# input2.net
KiCad netlist of a schematic drawn in Altium Designer
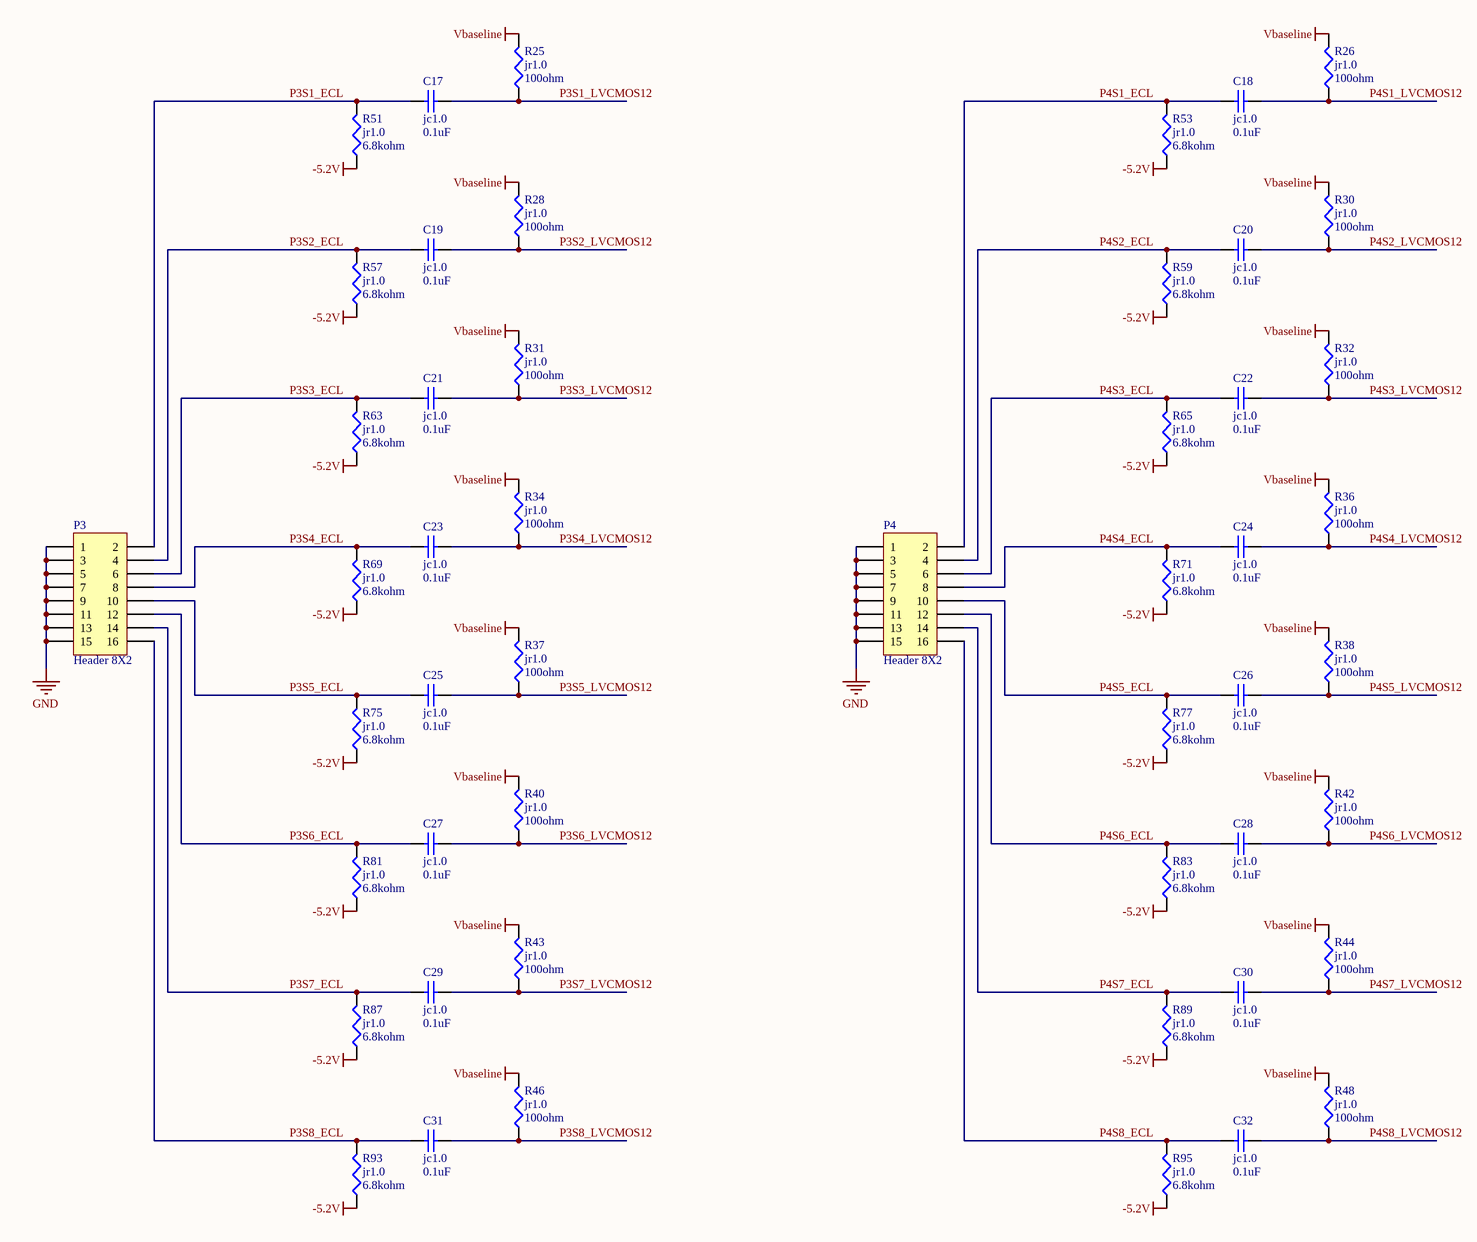
[diagram p0: input2.SchDoc]

(export (version "E")
  (design (tool "Eeschema 10.0.6"))
  (components
    (comp (ref "C17")
      (value "jc1.0")
      (footprint "0402")
      (description "Capacitor")
      (fields (field (name "ALTIUM_VALUE") "0.1uF") (field (name "PUBLISHER") "Altium Limited"))
      (libsource (lib "LIB01DXP2006SchLib") (part "Cap"))
    )
    (comp (ref "C18")
      (value "jc1.0")
      (footprint "0402")
      (description "Capacitor")
      (fields (field (name "ALTIUM_VALUE") "0.1uF") (field (name "PUBLISHER") "Altium Limited"))
      (libsource (lib "LIB01DXP2006SchLib") (part "Cap"))
    )
    (comp (ref "C19")
      (value "jc1.0")
      (footprint "0402")
      (description "Capacitor")
      (fields (field (name "ALTIUM_VALUE") "0.1uF") (field (name "PUBLISHER") "Altium Limited"))
      (libsource (lib "LIB01DXP2006SchLib") (part "Cap"))
    )
    (comp (ref "C20")
      (value "jc1.0")
      (footprint "0402")
      (description "Capacitor")
      (fields (field (name "ALTIUM_VALUE") "0.1uF") (field (name "PUBLISHER") "Altium Limited"))
      (libsource (lib "LIB01DXP2006SchLib") (part "Cap"))
    )
    (comp (ref "C21")
      (value "jc1.0")
      (footprint "0402")
      (description "Capacitor")
      (fields (field (name "ALTIUM_VALUE") "0.1uF") (field (name "PUBLISHER") "Altium Limited"))
      (libsource (lib "LIB01DXP2006SchLib") (part "Cap"))
    )
    (comp (ref "C22")
      (value "jc1.0")
      (footprint "0402")
      (description "Capacitor")
      (fields (field (name "ALTIUM_VALUE") "0.1uF") (field (name "PUBLISHER") "Altium Limited"))
      (libsource (lib "LIB01DXP2006SchLib") (part "Cap"))
    )
    (comp (ref "C23")
      (value "jc1.0")
      (footprint "0402")
      (description "Capacitor")
      (fields (field (name "ALTIUM_VALUE") "0.1uF") (field (name "PUBLISHER") "Altium Limited"))
      (libsource (lib "LIB01DXP2006SchLib") (part "Cap"))
    )
    (comp (ref "C24")
      (value "jc1.0")
      (footprint "0402")
      (description "Capacitor")
      (fields (field (name "ALTIUM_VALUE") "0.1uF") (field (name "PUBLISHER") "Altium Limited"))
      (libsource (lib "LIB01DXP2006SchLib") (part "Cap"))
    )
    (comp (ref "C25")
      (value "jc1.0")
      (footprint "0402")
      (description "Capacitor")
      (fields (field (name "ALTIUM_VALUE") "0.1uF") (field (name "PUBLISHER") "Altium Limited"))
      (libsource (lib "LIB01DXP2006SchLib") (part "Cap"))
    )
    (comp (ref "C26")
      (value "jc1.0")
      (footprint "0402")
      (description "Capacitor")
      (fields (field (name "ALTIUM_VALUE") "0.1uF") (field (name "PUBLISHER") "Altium Limited"))
      (libsource (lib "LIB01DXP2006SchLib") (part "Cap"))
    )
    (comp (ref "C27")
      (value "jc1.0")
      (footprint "0402")
      (description "Capacitor")
      (fields (field (name "ALTIUM_VALUE") "0.1uF") (field (name "PUBLISHER") "Altium Limited"))
      (libsource (lib "LIB01DXP2006SchLib") (part "Cap"))
    )
    (comp (ref "C28")
      (value "jc1.0")
      (footprint "0402")
      (description "Capacitor")
      (fields (field (name "ALTIUM_VALUE") "0.1uF") (field (name "PUBLISHER") "Altium Limited"))
      (libsource (lib "LIB01DXP2006SchLib") (part "Cap"))
    )
    (comp (ref "C29")
      (value "jc1.0")
      (footprint "0402")
      (description "Capacitor")
      (fields (field (name "ALTIUM_VALUE") "0.1uF") (field (name "PUBLISHER") "Altium Limited"))
      (libsource (lib "LIB01DXP2006SchLib") (part "Cap"))
    )
    (comp (ref "C30")
      (value "jc1.0")
      (footprint "0402")
      (description "Capacitor")
      (fields (field (name "ALTIUM_VALUE") "0.1uF") (field (name "PUBLISHER") "Altium Limited"))
      (libsource (lib "LIB01DXP2006SchLib") (part "Cap"))
    )
    (comp (ref "C31")
      (value "jc1.0")
      (footprint "0402")
      (description "Capacitor")
      (fields (field (name "ALTIUM_VALUE") "0.1uF") (field (name "PUBLISHER") "Altium Limited"))
      (libsource (lib "LIB01DXP2006SchLib") (part "Cap"))
    )
    (comp (ref "C32")
      (value "jc1.0")
      (footprint "0402")
      (description "Capacitor")
      (fields (field (name "ALTIUM_VALUE") "0.1uF") (field (name "PUBLISHER") "Altium Limited"))
      (libsource (lib "LIB01DXP2006SchLib") (part "Cap"))
    )
    (comp (ref "P3")
      (value "Header 8X2")
      (footprint "HDR2X8")
      (description "Header, 8-Pin, Dual row")
      (fields (field (name "PUBLISHER") "Altium Limited"))
      (libsource (lib "Miscellaneous Connectors") (part "Header 8X2"))
    )
    (comp (ref "P4")
      (value "Header 8X2")
      (footprint "HDR2X8")
      (description "Header, 8-Pin, Dual row")
      (fields (field (name "PUBLISHER") "Altium Limited"))
      (libsource (lib "Miscellaneous Connectors") (part "Header 8X2"))
    )
    (comp (ref "R25")
      (value "jr1.0")
      (footprint "0402")
      (description "Resistor")
      (fields (field (name "ALTIUM_VALUE") "100ohm") (field (name "PUBLISHER") "Altium Limited"))
      (libsource (lib "LIB01DXP2006SchLib") (part "Res"))
    )
    (comp (ref "R26")
      (value "jr1.0")
      (footprint "0402")
      (description "Resistor")
      (fields (field (name "ALTIUM_VALUE") "100ohm") (field (name "PUBLISHER") "Altium Limited"))
      (libsource (lib "LIB01DXP2006SchLib") (part "Res"))
    )
    (comp (ref "R28")
      (value "jr1.0")
      (footprint "0402")
      (description "Resistor")
      (fields (field (name "ALTIUM_VALUE") "100ohm") (field (name "PUBLISHER") "Altium Limited"))
      (libsource (lib "LIB01DXP2006SchLib") (part "Res"))
    )
    (comp (ref "R30")
      (value "jr1.0")
      (footprint "0402")
      (description "Resistor")
      (fields (field (name "ALTIUM_VALUE") "100ohm") (field (name "PUBLISHER") "Altium Limited"))
      (libsource (lib "LIB01DXP2006SchLib") (part "Res"))
    )
    (comp (ref "R31")
      (value "jr1.0")
      (footprint "0402")
      (description "Resistor")
      (fields (field (name "ALTIUM_VALUE") "100ohm") (field (name "PUBLISHER") "Altium Limited"))
      (libsource (lib "LIB01DXP2006SchLib") (part "Res"))
    )
    (comp (ref "R32")
      (value "jr1.0")
      (footprint "0402")
      (description "Resistor")
      (fields (field (name "ALTIUM_VALUE") "100ohm") (field (name "PUBLISHER") "Altium Limited"))
      (libsource (lib "LIB01DXP2006SchLib") (part "Res"))
    )
    (comp (ref "R34")
      (value "jr1.0")
      (footprint "0402")
      (description "Resistor")
      (fields (field (name "ALTIUM_VALUE") "100ohm") (field (name "PUBLISHER") "Altium Limited"))
      (libsource (lib "LIB01DXP2006SchLib") (part "Res"))
    )
    (comp (ref "R36")
      (value "jr1.0")
      (footprint "0402")
      (description "Resistor")
      (fields (field (name "ALTIUM_VALUE") "100ohm") (field (name "PUBLISHER") "Altium Limited"))
      (libsource (lib "LIB01DXP2006SchLib") (part "Res"))
    )
    (comp (ref "R37")
      (value "jr1.0")
      (footprint "0402")
      (description "Resistor")
      (fields (field (name "ALTIUM_VALUE") "100ohm") (field (name "PUBLISHER") "Altium Limited"))
      (libsource (lib "LIB01DXP2006SchLib") (part "Res"))
    )
    (comp (ref "R38")
      (value "jr1.0")
      (footprint "0402")
      (description "Resistor")
      (fields (field (name "ALTIUM_VALUE") "100ohm") (field (name "PUBLISHER") "Altium Limited"))
      (libsource (lib "LIB01DXP2006SchLib") (part "Res"))
    )
    (comp (ref "R40")
      (value "jr1.0")
      (footprint "0402")
      (description "Resistor")
      (fields (field (name "ALTIUM_VALUE") "100ohm") (field (name "PUBLISHER") "Altium Limited"))
      (libsource (lib "LIB01DXP2006SchLib") (part "Res"))
    )
    (comp (ref "R42")
      (value "jr1.0")
      (footprint "0402")
      (description "Resistor")
      (fields (field (name "ALTIUM_VALUE") "100ohm") (field (name "PUBLISHER") "Altium Limited"))
      (libsource (lib "LIB01DXP2006SchLib") (part "Res"))
    )
    (comp (ref "R43")
      (value "jr1.0")
      (footprint "0402")
      (description "Resistor")
      (fields (field (name "ALTIUM_VALUE") "100ohm") (field (name "PUBLISHER") "Altium Limited"))
      (libsource (lib "LIB01DXP2006SchLib") (part "Res"))
    )
    (comp (ref "R44")
      (value "jr1.0")
      (footprint "0402")
      (description "Resistor")
      (fields (field (name "ALTIUM_VALUE") "100ohm") (field (name "PUBLISHER") "Altium Limited"))
      (libsource (lib "LIB01DXP2006SchLib") (part "Res"))
    )
    (comp (ref "R46")
      (value "jr1.0")
      (footprint "0402")
      (description "Resistor")
      (fields (field (name "ALTIUM_VALUE") "100ohm") (field (name "PUBLISHER") "Altium Limited"))
      (libsource (lib "LIB01DXP2006SchLib") (part "Res"))
    )
    (comp (ref "R48")
      (value "jr1.0")
      (footprint "0402")
      (description "Resistor")
      (fields (field (name "ALTIUM_VALUE") "100ohm") (field (name "PUBLISHER") "Altium Limited"))
      (libsource (lib "LIB01DXP2006SchLib") (part "Res"))
    )
    (comp (ref "R51")
      (value "jr1.0")
      (footprint "0402")
      (description "Resistor")
      (fields (field (name "ALTIUM_VALUE") "6.8kohm") (field (name "PUBLISHER") "Altium Limited"))
      (libsource (lib "LIB01DXP2006SchLib") (part "Res"))
    )
    (comp (ref "R53")
      (value "jr1.0")
      (footprint "0402")
      (description "Resistor")
      (fields (field (name "ALTIUM_VALUE") "6.8kohm") (field (name "PUBLISHER") "Altium Limited"))
      (libsource (lib "LIB01DXP2006SchLib") (part "Res"))
    )
    (comp (ref "R57")
      (value "jr1.0")
      (footprint "0402")
      (description "Resistor")
      (fields (field (name "ALTIUM_VALUE") "6.8kohm") (field (name "PUBLISHER") "Altium Limited"))
      (libsource (lib "LIB01DXP2006SchLib") (part "Res"))
    )
    (comp (ref "R59")
      (value "jr1.0")
      (footprint "0402")
      (description "Resistor")
      (fields (field (name "ALTIUM_VALUE") "6.8kohm") (field (name "PUBLISHER") "Altium Limited"))
      (libsource (lib "LIB01DXP2006SchLib") (part "Res"))
    )
    (comp (ref "R63")
      (value "jr1.0")
      (footprint "0402")
      (description "Resistor")
      (fields (field (name "ALTIUM_VALUE") "6.8kohm") (field (name "PUBLISHER") "Altium Limited"))
      (libsource (lib "LIB01DXP2006SchLib") (part "Res"))
    )
    (comp (ref "R65")
      (value "jr1.0")
      (footprint "0402")
      (description "Resistor")
      (fields (field (name "ALTIUM_VALUE") "6.8kohm") (field (name "PUBLISHER") "Altium Limited"))
      (libsource (lib "LIB01DXP2006SchLib") (part "Res"))
    )
    (comp (ref "R69")
      (value "jr1.0")
      (footprint "0402")
      (description "Resistor")
      (fields (field (name "ALTIUM_VALUE") "6.8kohm") (field (name "PUBLISHER") "Altium Limited"))
      (libsource (lib "LIB01DXP2006SchLib") (part "Res"))
    )
    (comp (ref "R71")
      (value "jr1.0")
      (footprint "0402")
      (description "Resistor")
      (fields (field (name "ALTIUM_VALUE") "6.8kohm") (field (name "PUBLISHER") "Altium Limited"))
      (libsource (lib "LIB01DXP2006SchLib") (part "Res"))
    )
    (comp (ref "R75")
      (value "jr1.0")
      (footprint "0402")
      (description "Resistor")
      (fields (field (name "ALTIUM_VALUE") "6.8kohm") (field (name "PUBLISHER") "Altium Limited"))
      (libsource (lib "LIB01DXP2006SchLib") (part "Res"))
    )
    (comp (ref "R77")
      (value "jr1.0")
      (footprint "0402")
      (description "Resistor")
      (fields (field (name "ALTIUM_VALUE") "6.8kohm") (field (name "PUBLISHER") "Altium Limited"))
      (libsource (lib "LIB01DXP2006SchLib") (part "Res"))
    )
    (comp (ref "R81")
      (value "jr1.0")
      (footprint "0402")
      (description "Resistor")
      (fields (field (name "ALTIUM_VALUE") "6.8kohm") (field (name "PUBLISHER") "Altium Limited"))
      (libsource (lib "LIB01DXP2006SchLib") (part "Res"))
    )
    (comp (ref "R83")
      (value "jr1.0")
      (footprint "0402")
      (description "Resistor")
      (fields (field (name "ALTIUM_VALUE") "6.8kohm") (field (name "PUBLISHER") "Altium Limited"))
      (libsource (lib "LIB01DXP2006SchLib") (part "Res"))
    )
    (comp (ref "R87")
      (value "jr1.0")
      (footprint "0402")
      (description "Resistor")
      (fields (field (name "ALTIUM_VALUE") "6.8kohm") (field (name "PUBLISHER") "Altium Limited"))
      (libsource (lib "LIB01DXP2006SchLib") (part "Res"))
    )
    (comp (ref "R89")
      (value "jr1.0")
      (footprint "0402")
      (description "Resistor")
      (fields (field (name "ALTIUM_VALUE") "6.8kohm") (field (name "PUBLISHER") "Altium Limited"))
      (libsource (lib "LIB01DXP2006SchLib") (part "Res"))
    )
    (comp (ref "R93")
      (value "jr1.0")
      (footprint "0402")
      (description "Resistor")
      (fields (field (name "ALTIUM_VALUE") "6.8kohm") (field (name "PUBLISHER") "Altium Limited"))
      (libsource (lib "LIB01DXP2006SchLib") (part "Res"))
    )
    (comp (ref "R95")
      (value "jr1.0")
      (footprint "0402")
      (description "Resistor")
      (fields (field (name "ALTIUM_VALUE") "6.8kohm") (field (name "PUBLISHER") "Altium Limited"))
      (libsource (lib "LIB01DXP2006SchLib") (part "Res"))
    )
  )
  (nets
    (net (code "1") (name "-5.2V") (class "Default")
      (node (ref "R51") (pin "1") (pinfunction "1_1") (pintype "passive"))
      (node (ref "R53") (pin "1") (pinfunction "1_1") (pintype "passive"))
      (node (ref "R57") (pin "1") (pinfunction "1_1") (pintype "passive"))
      (node (ref "R59") (pin "1") (pinfunction "1_1") (pintype "passive"))
      (node (ref "R63") (pin "1") (pinfunction "1_1") (pintype "passive"))
      (node (ref "R65") (pin "1") (pinfunction "1_1") (pintype "passive"))
      (node (ref "R69") (pin "1") (pinfunction "1_1") (pintype "passive"))
      (node (ref "R71") (pin "1") (pinfunction "1_1") (pintype "passive"))
      (node (ref "R75") (pin "1") (pinfunction "1_1") (pintype "passive"))
      (node (ref "R77") (pin "1") (pinfunction "1_1") (pintype "passive"))
      (node (ref "R81") (pin "1") (pinfunction "1_1") (pintype "passive"))
      (node (ref "R83") (pin "1") (pinfunction "1_1") (pintype "passive"))
      (node (ref "R87") (pin "1") (pinfunction "1_1") (pintype "passive"))
      (node (ref "R89") (pin "1") (pinfunction "1_1") (pintype "passive"))
      (node (ref "R93") (pin "1") (pinfunction "1_1") (pintype "passive"))
      (node (ref "R95") (pin "1") (pinfunction "1_1") (pintype "passive"))
    )
    (net (code "2") (name "/P3S1_ECL") (class "Default")
      (node (ref "C17") (pin "1") (pinfunction "1_1") (pintype "passive"))
      (node (ref "P3") (pin "2") (pinfunction "2_2") (pintype "passive"))
      (node (ref "R51") (pin "2") (pinfunction "2_2") (pintype "passive"))
    )
    (net (code "3") (name "/P3S1_LVCMOS12") (class "Default")
      (node (ref "C17") (pin "2") (pinfunction "2_2") (pintype "passive"))
      (node (ref "R25") (pin "1") (pinfunction "1_1") (pintype "passive"))
    )
    (net (code "4") (name "/P3S2_ECL") (class "Default")
      (node (ref "C19") (pin "1") (pinfunction "1_1") (pintype "passive"))
      (node (ref "P3") (pin "4") (pinfunction "4_4") (pintype "passive"))
      (node (ref "R57") (pin "2") (pinfunction "2_2") (pintype "passive"))
    )
    (net (code "5") (name "/P3S2_LVCMOS12") (class "Default")
      (node (ref "C19") (pin "2") (pinfunction "2_2") (pintype "passive"))
      (node (ref "R28") (pin "1") (pinfunction "1_1") (pintype "passive"))
    )
    (net (code "6") (name "/P3S3_ECL") (class "Default")
      (node (ref "C21") (pin "1") (pinfunction "1_1") (pintype "passive"))
      (node (ref "P3") (pin "6") (pinfunction "6_6") (pintype "passive"))
      (node (ref "R63") (pin "2") (pinfunction "2_2") (pintype "passive"))
    )
    (net (code "7") (name "/P3S3_LVCMOS12") (class "Default")
      (node (ref "C21") (pin "2") (pinfunction "2_2") (pintype "passive"))
      (node (ref "R31") (pin "1") (pinfunction "1_1") (pintype "passive"))
    )
    (net (code "8") (name "/P3S4_ECL") (class "Default")
      (node (ref "C23") (pin "1") (pinfunction "1_1") (pintype "passive"))
      (node (ref "P3") (pin "8") (pinfunction "8_8") (pintype "passive"))
      (node (ref "R69") (pin "2") (pinfunction "2_2") (pintype "passive"))
    )
    (net (code "9") (name "/P3S4_LVCMOS12") (class "Default")
      (node (ref "C23") (pin "2") (pinfunction "2_2") (pintype "passive"))
      (node (ref "R34") (pin "1") (pinfunction "1_1") (pintype "passive"))
    )
    (net (code "10") (name "/P3S5_ECL") (class "Default")
      (node (ref "C25") (pin "1") (pinfunction "1_1") (pintype "passive"))
      (node (ref "P3") (pin "10") (pinfunction "10_10") (pintype "passive"))
      (node (ref "R75") (pin "2") (pinfunction "2_2") (pintype "passive"))
    )
    (net (code "11") (name "/P3S5_LVCMOS12") (class "Default")
      (node (ref "C25") (pin "2") (pinfunction "2_2") (pintype "passive"))
      (node (ref "R37") (pin "1") (pinfunction "1_1") (pintype "passive"))
    )
    (net (code "12") (name "/P3S6_ECL") (class "Default")
      (node (ref "C27") (pin "1") (pinfunction "1_1") (pintype "passive"))
      (node (ref "P3") (pin "12") (pinfunction "12_12") (pintype "passive"))
      (node (ref "R81") (pin "2") (pinfunction "2_2") (pintype "passive"))
    )
    (net (code "13") (name "/P3S6_LVCMOS12") (class "Default")
      (node (ref "C27") (pin "2") (pinfunction "2_2") (pintype "passive"))
      (node (ref "R40") (pin "1") (pinfunction "1_1") (pintype "passive"))
    )
    (net (code "14") (name "/P3S7_ECL") (class "Default")
      (node (ref "C29") (pin "1") (pinfunction "1_1") (pintype "passive"))
      (node (ref "P3") (pin "14") (pinfunction "14_14") (pintype "passive"))
      (node (ref "R87") (pin "2") (pinfunction "2_2") (pintype "passive"))
    )
    (net (code "15") (name "/P3S7_LVCMOS12") (class "Default")
      (node (ref "C29") (pin "2") (pinfunction "2_2") (pintype "passive"))
      (node (ref "R43") (pin "1") (pinfunction "1_1") (pintype "passive"))
    )
    (net (code "16") (name "/P3S8_ECL") (class "Default")
      (node (ref "C31") (pin "1") (pinfunction "1_1") (pintype "passive"))
      (node (ref "P3") (pin "16") (pinfunction "16_16") (pintype "passive"))
      (node (ref "R93") (pin "2") (pinfunction "2_2") (pintype "passive"))
    )
    (net (code "17") (name "/P3S8_LVCMOS12") (class "Default")
      (node (ref "C31") (pin "2") (pinfunction "2_2") (pintype "passive"))
      (node (ref "R46") (pin "1") (pinfunction "1_1") (pintype "passive"))
    )
    (net (code "18") (name "/P4S1_ECL") (class "Default")
      (node (ref "C18") (pin "1") (pinfunction "1_1") (pintype "passive"))
      (node (ref "P4") (pin "2") (pinfunction "2_2") (pintype "passive"))
      (node (ref "R53") (pin "2") (pinfunction "2_2") (pintype "passive"))
    )
    (net (code "19") (name "/P4S1_LVCMOS12") (class "Default")
      (node (ref "C18") (pin "2") (pinfunction "2_2") (pintype "passive"))
      (node (ref "R26") (pin "1") (pinfunction "1_1") (pintype "passive"))
    )
    (net (code "20") (name "/P4S2_ECL") (class "Default")
      (node (ref "C20") (pin "1") (pinfunction "1_1") (pintype "passive"))
      (node (ref "P4") (pin "4") (pinfunction "4_4") (pintype "passive"))
      (node (ref "R59") (pin "2") (pinfunction "2_2") (pintype "passive"))
    )
    (net (code "21") (name "/P4S2_LVCMOS12") (class "Default")
      (node (ref "C20") (pin "2") (pinfunction "2_2") (pintype "passive"))
      (node (ref "R30") (pin "1") (pinfunction "1_1") (pintype "passive"))
    )
    (net (code "22") (name "/P4S3_ECL") (class "Default")
      (node (ref "C22") (pin "1") (pinfunction "1_1") (pintype "passive"))
      (node (ref "P4") (pin "6") (pinfunction "6_6") (pintype "passive"))
      (node (ref "R65") (pin "2") (pinfunction "2_2") (pintype "passive"))
    )
    (net (code "23") (name "/P4S3_LVCMOS12") (class "Default")
      (node (ref "C22") (pin "2") (pinfunction "2_2") (pintype "passive"))
      (node (ref "R32") (pin "1") (pinfunction "1_1") (pintype "passive"))
    )
    (net (code "24") (name "/P4S4_ECL") (class "Default")
      (node (ref "C24") (pin "1") (pinfunction "1_1") (pintype "passive"))
      (node (ref "P4") (pin "8") (pinfunction "8_8") (pintype "passive"))
      (node (ref "R71") (pin "2") (pinfunction "2_2") (pintype "passive"))
    )
    (net (code "25") (name "/P4S4_LVCMOS12") (class "Default")
      (node (ref "C24") (pin "2") (pinfunction "2_2") (pintype "passive"))
      (node (ref "R36") (pin "1") (pinfunction "1_1") (pintype "passive"))
    )
    (net (code "26") (name "/P4S5_ECL") (class "Default")
      (node (ref "C26") (pin "1") (pinfunction "1_1") (pintype "passive"))
      (node (ref "P4") (pin "10") (pinfunction "10_10") (pintype "passive"))
      (node (ref "R77") (pin "2") (pinfunction "2_2") (pintype "passive"))
    )
    (net (code "27") (name "/P4S5_LVCMOS12") (class "Default")
      (node (ref "C26") (pin "2") (pinfunction "2_2") (pintype "passive"))
      (node (ref "R38") (pin "1") (pinfunction "1_1") (pintype "passive"))
    )
    (net (code "28") (name "/P4S6_ECL") (class "Default")
      (node (ref "C28") (pin "1") (pinfunction "1_1") (pintype "passive"))
      (node (ref "P4") (pin "12") (pinfunction "12_12") (pintype "passive"))
      (node (ref "R83") (pin "2") (pinfunction "2_2") (pintype "passive"))
    )
    (net (code "29") (name "/P4S6_LVCMOS12") (class "Default")
      (node (ref "C28") (pin "2") (pinfunction "2_2") (pintype "passive"))
      (node (ref "R42") (pin "1") (pinfunction "1_1") (pintype "passive"))
    )
    (net (code "30") (name "/P4S7_ECL") (class "Default")
      (node (ref "C30") (pin "1") (pinfunction "1_1") (pintype "passive"))
      (node (ref "P4") (pin "14") (pinfunction "14_14") (pintype "passive"))
      (node (ref "R89") (pin "2") (pinfunction "2_2") (pintype "passive"))
    )
    (net (code "31") (name "/P4S7_LVCMOS12") (class "Default")
      (node (ref "C30") (pin "2") (pinfunction "2_2") (pintype "passive"))
      (node (ref "R44") (pin "1") (pinfunction "1_1") (pintype "passive"))
    )
    (net (code "32") (name "/P4S8_ECL") (class "Default")
      (node (ref "C32") (pin "1") (pinfunction "1_1") (pintype "passive"))
      (node (ref "P4") (pin "16") (pinfunction "16_16") (pintype "passive"))
      (node (ref "R95") (pin "2") (pinfunction "2_2") (pintype "passive"))
    )
    (net (code "33") (name "/P4S8_LVCMOS12") (class "Default")
      (node (ref "C32") (pin "2") (pinfunction "2_2") (pintype "passive"))
      (node (ref "R48") (pin "1") (pinfunction "1_1") (pintype "passive"))
    )
    (net (code "34") (name "GND") (class "Default")
      (node (ref "P3") (pin "1") (pinfunction "1_1") (pintype "passive"))
      (node (ref "P3") (pin "11") (pinfunction "11_11") (pintype "passive"))
      (node (ref "P3") (pin "13") (pinfunction "13_13") (pintype "passive"))
      (node (ref "P3") (pin "15") (pinfunction "15_15") (pintype "passive"))
      (node (ref "P3") (pin "3") (pinfunction "3_3") (pintype "passive"))
      (node (ref "P3") (pin "5") (pinfunction "5_5") (pintype "passive"))
      (node (ref "P3") (pin "7") (pinfunction "7_7") (pintype "passive"))
      (node (ref "P3") (pin "9") (pinfunction "9_9") (pintype "passive"))
      (node (ref "P4") (pin "1") (pinfunction "1_1") (pintype "passive"))
      (node (ref "P4") (pin "11") (pinfunction "11_11") (pintype "passive"))
      (node (ref "P4") (pin "13") (pinfunction "13_13") (pintype "passive"))
      (node (ref "P4") (pin "15") (pinfunction "15_15") (pintype "passive"))
      (node (ref "P4") (pin "3") (pinfunction "3_3") (pintype "passive"))
      (node (ref "P4") (pin "5") (pinfunction "5_5") (pintype "passive"))
      (node (ref "P4") (pin "7") (pinfunction "7_7") (pintype "passive"))
      (node (ref "P4") (pin "9") (pinfunction "9_9") (pintype "passive"))
    )
    (net (code "35") (name "Vbaseline") (class "Default")
      (node (ref "R25") (pin "2") (pinfunction "2_2") (pintype "passive"))
      (node (ref "R26") (pin "2") (pinfunction "2_2") (pintype "passive"))
      (node (ref "R28") (pin "2") (pinfunction "2_2") (pintype "passive"))
      (node (ref "R30") (pin "2") (pinfunction "2_2") (pintype "passive"))
      (node (ref "R31") (pin "2") (pinfunction "2_2") (pintype "passive"))
      (node (ref "R32") (pin "2") (pinfunction "2_2") (pintype "passive"))
      (node (ref "R34") (pin "2") (pinfunction "2_2") (pintype "passive"))
      (node (ref "R36") (pin "2") (pinfunction "2_2") (pintype "passive"))
      (node (ref "R37") (pin "2") (pinfunction "2_2") (pintype "passive"))
      (node (ref "R38") (pin "2") (pinfunction "2_2") (pintype "passive"))
      (node (ref "R40") (pin "2") (pinfunction "2_2") (pintype "passive"))
      (node (ref "R42") (pin "2") (pinfunction "2_2") (pintype "passive"))
      (node (ref "R43") (pin "2") (pinfunction "2_2") (pintype "passive"))
      (node (ref "R44") (pin "2") (pinfunction "2_2") (pintype "passive"))
      (node (ref "R46") (pin "2") (pinfunction "2_2") (pintype "passive"))
      (node (ref "R48") (pin "2") (pinfunction "2_2") (pintype "passive"))
    )
  )
)
